# cdh.net
KiCad netlist of a schematic drawn in Altium Designer
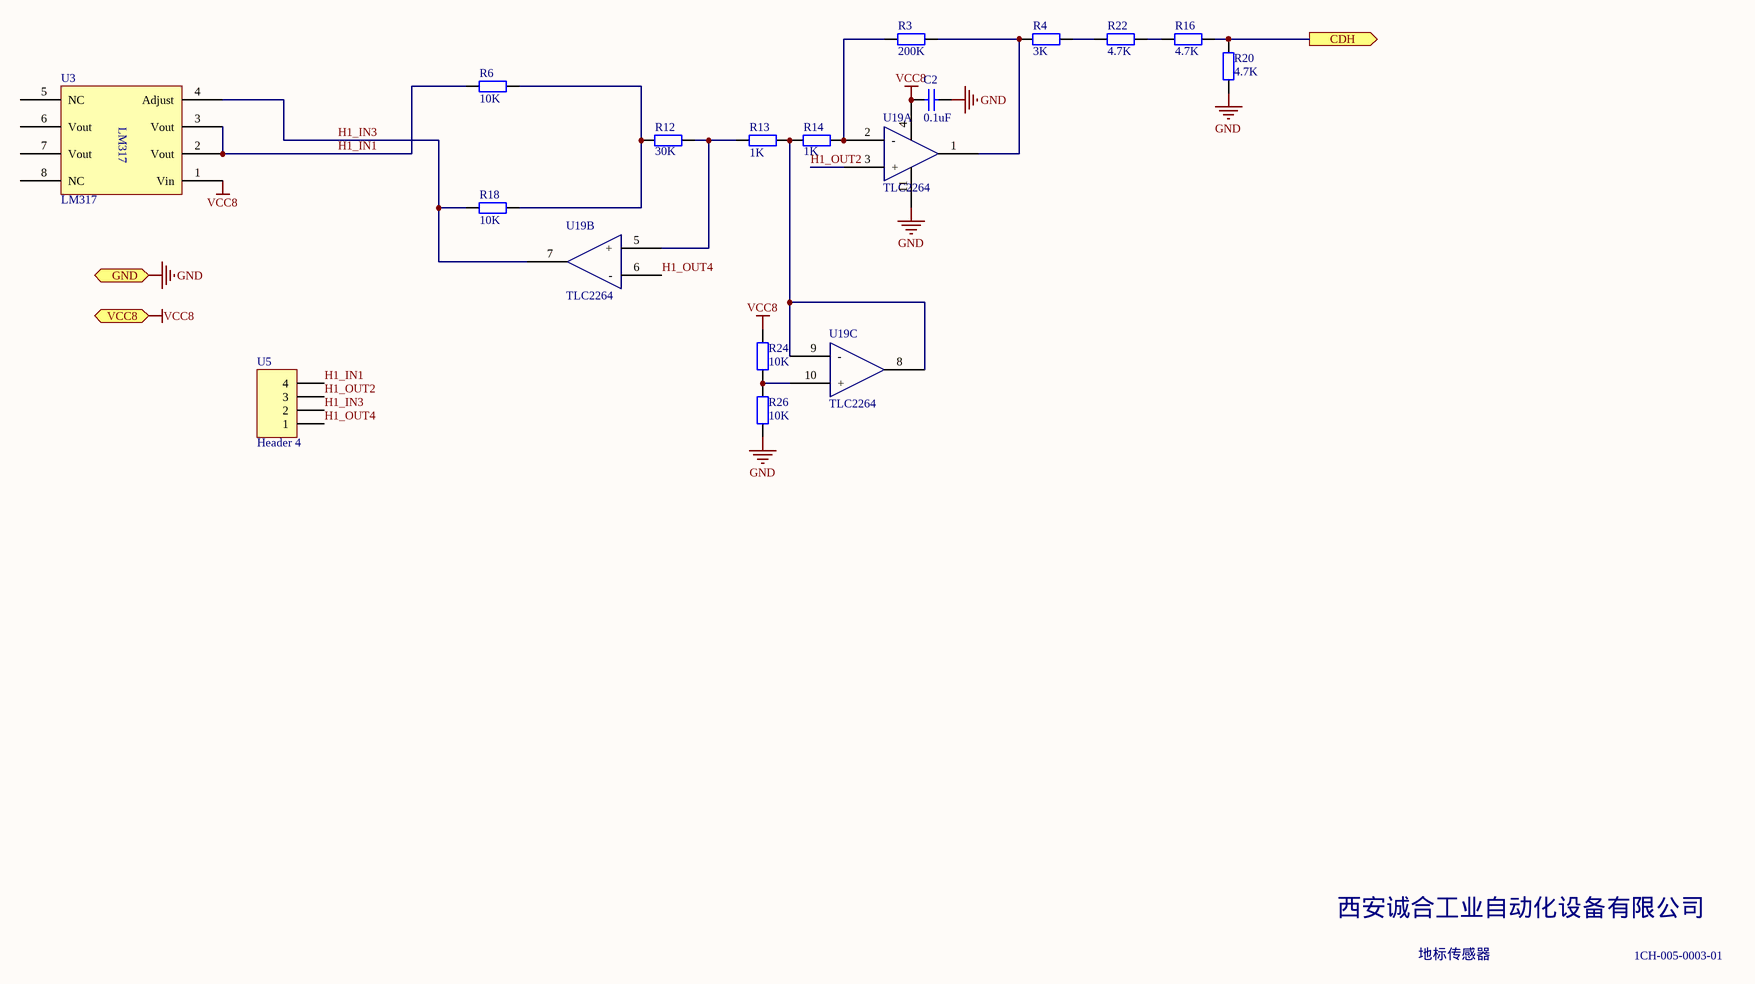
[diagram p0: cdh.SchDoc]

(export (version "E")
  (design (tool "Eeschema 10.0.6"))
  (components
    (comp (ref "C2")
      (value "0.1uF")
      (footprint "C0805")
      (description "Capacitor (Semiconductor SIM Model)")
      (fields (field (name "PUBLISHER") "Altium Limited"))
      (libsource (lib "Miscellaneous Devices") (part "Cap Semi"))
    )
    (comp (ref "R3")
      (value "200K")
      (footprint "0603_R")
      (description "Resistor")
      (fields (field (name "PUBLISHER") "Altium Limited"))
      (libsource (lib "Miscellaneous Devices") (part "Res2"))
    )
    (comp (ref "R4")
      (value "3K")
      (footprint "0603_R")
      (description "Resistor")
      (fields (field (name "PUBLISHER") "Altium Limited"))
      (libsource (lib "Miscellaneous Devices") (part "Res2"))
    )
    (comp (ref "R6")
      (value "10K")
      (footprint "0603_R")
      (description "Resistor")
      (fields (field (name "PUBLISHER") "Altium Limited"))
      (libsource (lib "Miscellaneous Devices") (part "Res2"))
    )
    (comp (ref "R12")
      (value "30K")
      (footprint "0603_R")
      (description "Resistor")
      (fields (field (name "PUBLISHER") "Altium Limited"))
      (libsource (lib "Miscellaneous Devices") (part "Res2"))
    )
    (comp (ref "R13")
      (value "1K")
      (footprint "0603_R")
      (description "Resistor")
      (fields (field (name "PUBLISHER") "Altium Limited"))
      (libsource (lib "Miscellaneous Devices") (part "Res2"))
    )
    (comp (ref "R14")
      (value "1K")
      (footprint "0603_R")
      (description "Resistor")
      (fields (field (name "PUBLISHER") "Altium Limited"))
      (libsource (lib "") (part "Res2_2"))
    )
    (comp (ref "R16")
      (value "4.7K")
      (footprint "0603")
      (description "Resistor")
      (fields (field (name "PUBLISHER") "Altium Limited"))
      (libsource (lib "Miscellaneous Devices") (part "Res2"))
    )
    (comp (ref "R18")
      (value "10K")
      (footprint "0603_R")
      (description "Resistor")
      (fields (field (name "PUBLISHER") "Altium Limited"))
      (libsource (lib "Miscellaneous Devices") (part "Res2"))
    )
    (comp (ref "R20")
      (value "4.7K")
      (footprint "0603")
      (description "Resistor")
      (fields (field (name "PUBLISHER") "Altium Limited"))
      (libsource (lib "") (part "Res2_1"))
    )
    (comp (ref "R22")
      (value "4.7K")
      (footprint "0603_R")
      (description "Resistor")
      (fields (field (name "PUBLISHER") "Altium Limited"))
      (libsource (lib "Miscellaneous Devices") (part "Res2"))
    )
    (comp (ref "R24")
      (value "10K")
      (footprint "0603_R")
      (description "Resistor")
      (fields (field (name "PUBLISHER") "Altium Limited"))
      (libsource (lib "") (part "Res2_1"))
    )
    (comp (ref "R26")
      (value "10K")
      (footprint "0603_R")
      (description "Resistor")
      (fields (field (name "PUBLISHER") "Altium Limited"))
      (libsource (lib "") (part "Res2_1"))
    )
    (comp (ref "U3") (value "LM317") (footprint "SO-8") (libsource (lib "磁导航") (part "LM317")))
    (comp (ref "U5")
      (value "Header 4")
      (footprint "PIN4")
      (description "Header, 4-Pin")
      (fields (field (name "PUBLISHER") "Altium Limited"))
      (libsource (lib "Miscellaneous Connectors") (part "Header 4"))
    )
    (comp (ref "U19") (value "TLC2264") (footprint "TSSOP14") (libsource (lib "EXPLORER") (part "TLC2264")))
  )
  (nets
    (net (code "1") (name "/CDH") (class "Default")
      (node (ref "R16") (pin "2") (pinfunction "2_2") (pintype "passive"))
      (node (ref "R20") (pin "2") (pinfunction "2_2") (pintype "passive"))
    )
    (net (code "2") (name "/H1_IN1") (class "Default")
      (node (ref "R6") (pin "1") (pinfunction "1_1") (pintype "passive"))
      (node (ref "U3") (pin "2") (pinfunction "Vout_2") (pintype "passive"))
      (node (ref "U3") (pin "3") (pinfunction "Vout_3") (pintype "passive"))
      (node (ref "U5") (pin "4") (pinfunction "4_4") (pintype "passive"))
    )
    (net (code "3") (name "/H1_IN3") (class "Default")
      (node (ref "R18") (pin "1") (pinfunction "1_1") (pintype "passive"))
      (node (ref "U19") (pin "7") (pinfunction "2OUT_7") (pintype "passive"))
      (node (ref "U3") (pin "4") (pinfunction "Adjust_4") (pintype "passive"))
      (node (ref "U5") (pin "2") (pinfunction "2_2") (pintype "passive"))
    )
    (net (code "4") (name "/H1_OUT2") (class "Default")
      (node (ref "U19") (pin "3") (pinfunction "+_3") (pintype "passive"))
      (node (ref "U5") (pin "3") (pinfunction "3_3") (pintype "passive"))
    )
    (net (code "5") (name "/H1_OUT4") (class "Default")
      (node (ref "U19") (pin "6") (pinfunction "-_6") (pintype "passive"))
      (node (ref "U5") (pin "1") (pinfunction "1_1") (pintype "passive"))
    )
    (net (code "6") (name "GND") (class "Default")
      (node (ref "C2") (pin "1") (pinfunction "1_1") (pintype "passive"))
      (node (ref "R20") (pin "1") (pinfunction "1_1") (pintype "passive"))
      (node (ref "R26") (pin "1") (pinfunction "1_1") (pintype "passive"))
      (node (ref "U19") (pin "11") (pinfunction "GND_11") (pintype "passive"))
    )
    (net (code "7") (name "Net-(R12-Pad1)") (class "Default")
      (node (ref "R12") (pin "1") (pinfunction "1_1") (pintype "passive"))
      (node (ref "R18") (pin "2") (pinfunction "2_2") (pintype "passive"))
      (node (ref "R6") (pin "2") (pinfunction "2_2") (pintype "passive"))
    )
    (net (code "8") (name "Net-(R16-Pad1)") (class "Default")
      (node (ref "R16") (pin "1") (pinfunction "1_1") (pintype "passive"))
      (node (ref "R22") (pin "2") (pinfunction "2_2") (pintype "passive"))
    )
    (net (code "9") (name "Net-(R22-Pad1)") (class "Default")
      (node (ref "R22") (pin "1") (pinfunction "1_1") (pintype "passive"))
      (node (ref "R4") (pin "2") (pinfunction "2_2") (pintype "passive"))
    )
    (net (code "10") (name "Net-(U19A--)") (class "Default")
      (node (ref "R14") (pin "1") (pinfunction "1_1") (pintype "passive"))
      (node (ref "R3") (pin "1") (pinfunction "1_1") (pintype "passive"))
      (node (ref "U19") (pin "2") (pinfunction "-_2") (pintype "passive"))
    )
    (net (code "11") (name "Net-(U19A-1OUT)") (class "Default")
      (node (ref "R3") (pin "2") (pinfunction "2_2") (pintype "passive"))
      (node (ref "R4") (pin "1") (pinfunction "1_1") (pintype "passive"))
      (node (ref "U19") (pin "1") (pinfunction "1OUT_1") (pintype "passive"))
    )
    (net (code "12") (name "Net-(U19B-+)") (class "Default")
      (node (ref "R12") (pin "2") (pinfunction "2_2") (pintype "passive"))
      (node (ref "R13") (pin "1") (pinfunction "1_1") (pintype "passive"))
      (node (ref "U19") (pin "5") (pinfunction "+_5") (pintype "passive"))
    )
    (net (code "13") (name "Net-(U19C-+)") (class "Default")
      (node (ref "R24") (pin "1") (pinfunction "1_1") (pintype "passive"))
      (node (ref "R26") (pin "2") (pinfunction "2_2") (pintype "passive"))
      (node (ref "U19") (pin "10") (pinfunction "+_10") (pintype "passive"))
    )
    (net (code "14") (name "Net-(U19C--)") (class "Default")
      (node (ref "R13") (pin "2") (pinfunction "2_2") (pintype "passive"))
      (node (ref "R14") (pin "2") (pinfunction "2_2") (pintype "passive"))
      (node (ref "U19") (pin "8") (pinfunction "3OUT_8") (pintype "passive"))
      (node (ref "U19") (pin "9") (pinfunction "-_9") (pintype "passive"))
    )
    (net (code "15") (name "VCC8") (class "Default")
      (node (ref "C2") (pin "2") (pinfunction "2_2") (pintype "passive"))
      (node (ref "R24") (pin "2") (pinfunction "2_2") (pintype "passive"))
      (node (ref "U19") (pin "4") (pinfunction "VCC_4") (pintype "passive"))
      (node (ref "U3") (pin "1") (pinfunction "Vin_1") (pintype "passive"))
    )
    (net (code "16") (name "unconnected-(U3-NC-Pad5)") (class "Default")
      (node (ref "U3") (pin "5") (pinfunction "NC_5") (pintype "passive"))
    )
    (net (code "17") (name "unconnected-(U3-NC-Pad8)") (class "Default")
      (node (ref "U3") (pin "8") (pinfunction "NC_8") (pintype "passive"))
    )
    (net (code "18") (name "unconnected-(U3-Vout-Pad6)") (class "Default")
      (node (ref "U3") (pin "6") (pinfunction "Vout_6") (pintype "passive"))
    )
    (net (code "19") (name "unconnected-(U3-Vout-Pad7)") (class "Default")
      (node (ref "U3") (pin "7") (pinfunction "Vout_7") (pintype "passive"))
    )
  )
)
